# RFIDAccess.net
KiCad netlist of a schematic drawn in EAGLE
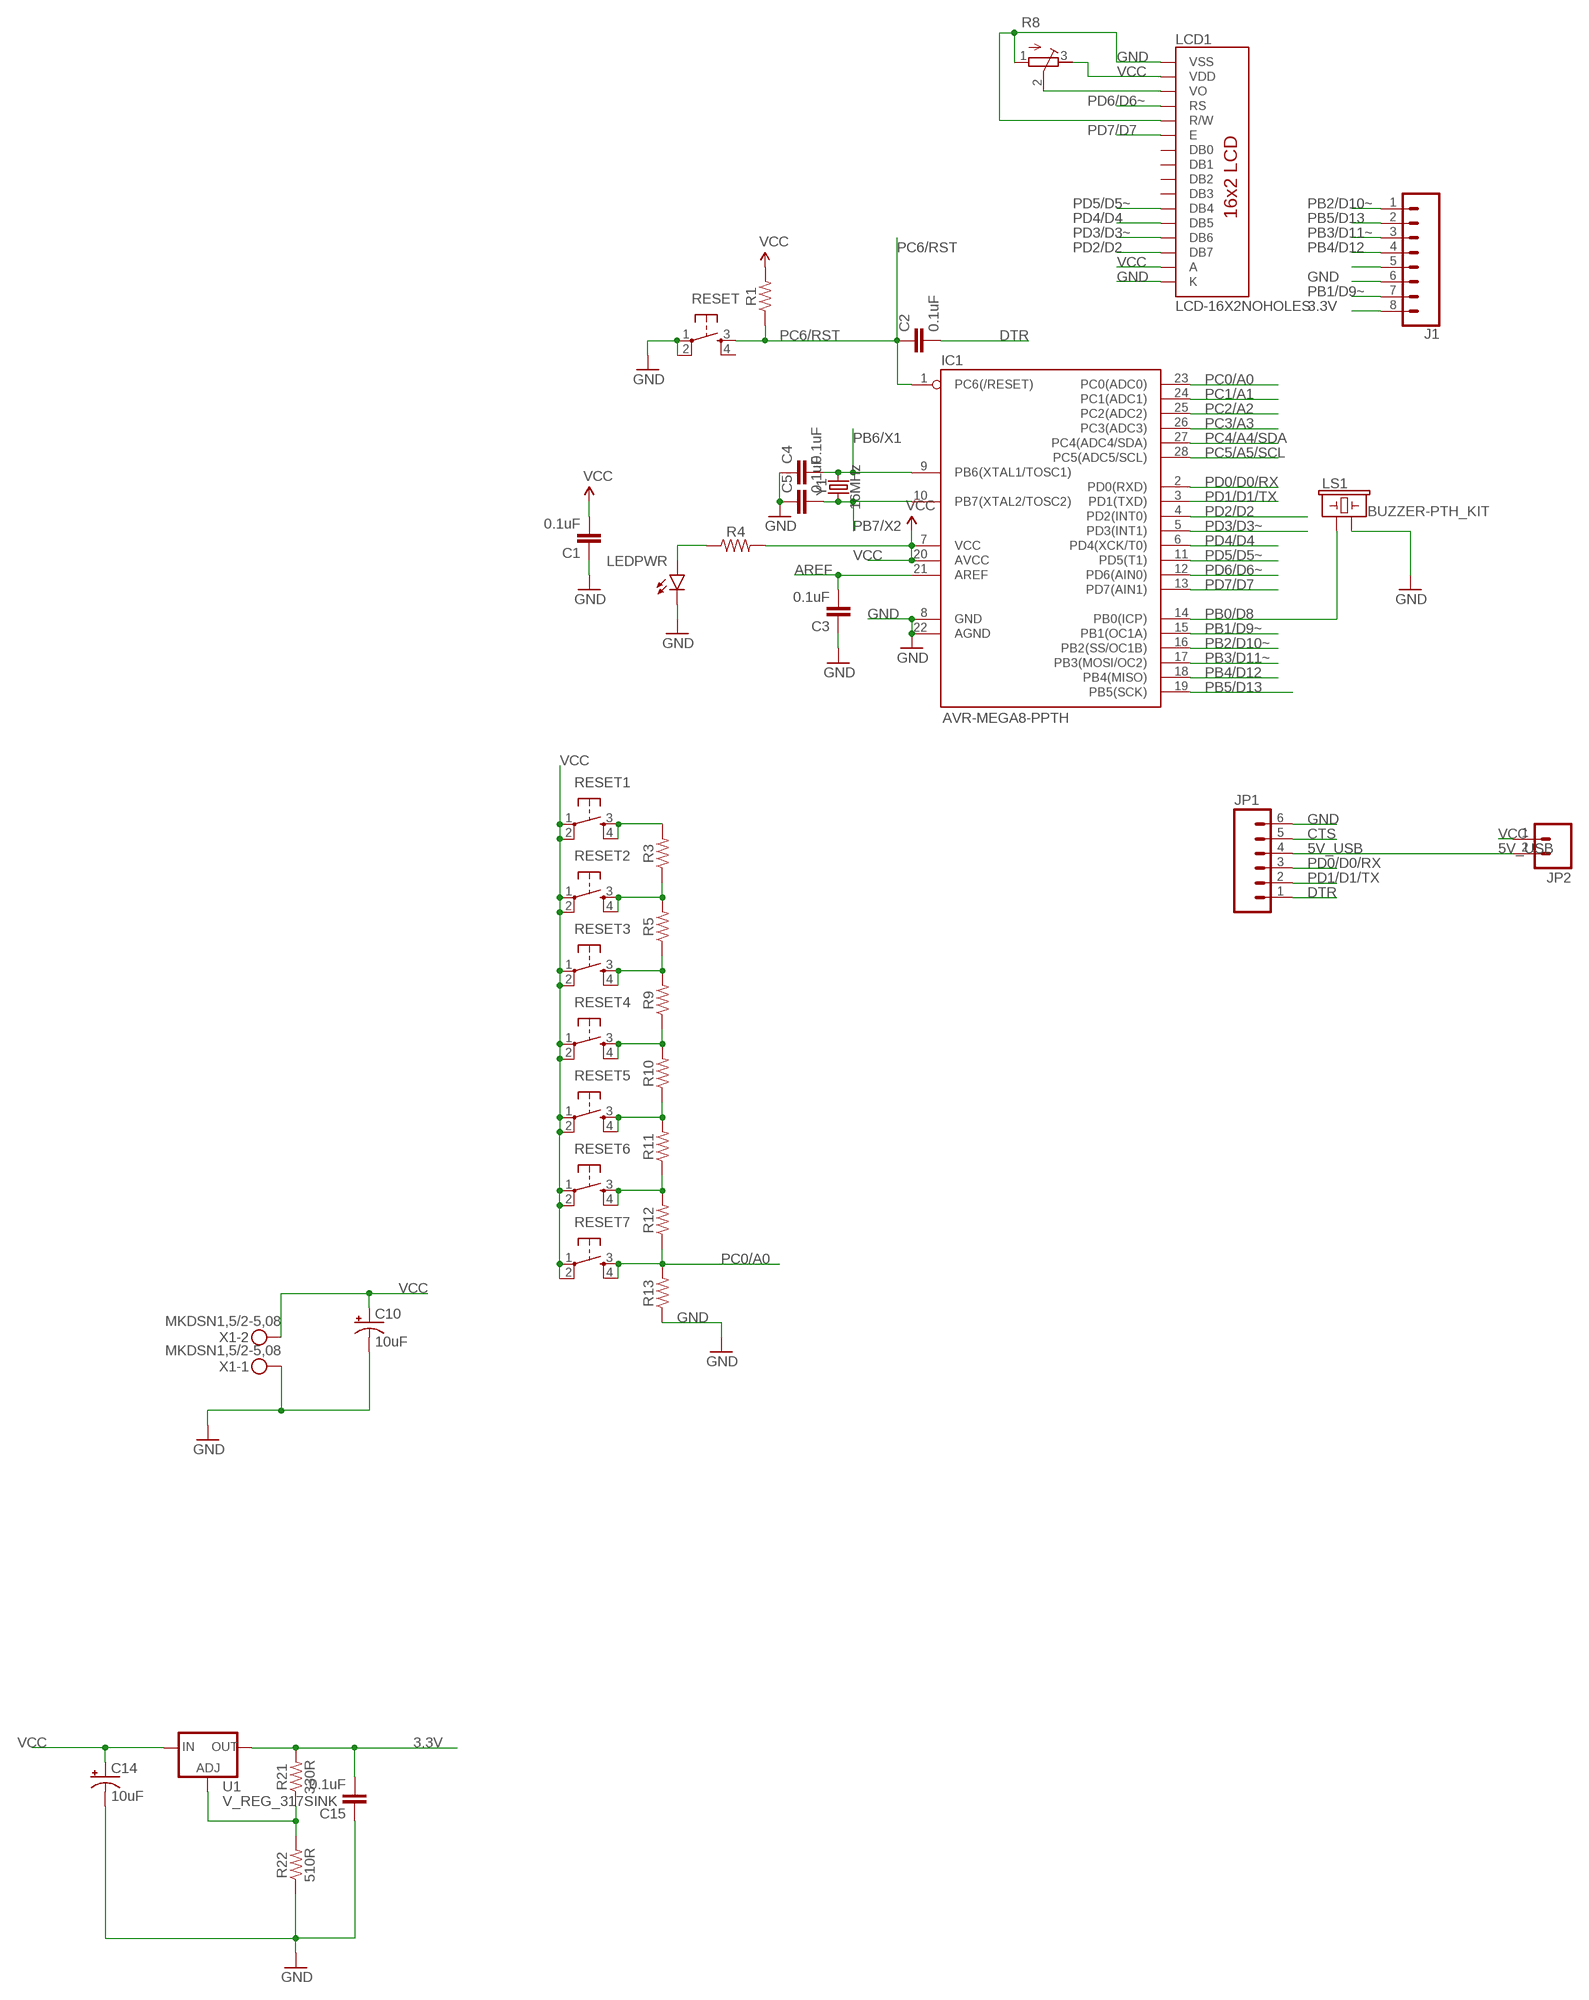
[diagram p0: schematic, sheet 1]

(export (version "E")
  (design (tool "Eeschema 10.0.6"))
  (components
    (comp (ref "C1")
      (value "0.1uF")
      (footprint "eagle-import:CAP-PTH-SMALL-KIT")
      (libsource (lib "eagle-import") (part "0.1UF-KIT-EZ-50V-20%"))
    )
    (comp (ref "C2")
      (value "0.1uF")
      (footprint "eagle-import:CAP-PTH-SMALL-KIT")
      (libsource (lib "eagle-import") (part "0.1UF-KIT-EZ-50V-20%"))
    )
    (comp (ref "C3")
      (value "0.1uF")
      (footprint "eagle-import:CAP-PTH-SMALL-KIT")
      (libsource (lib "eagle-import") (part "0.1UF-KIT-EZ-50V-20%"))
    )
    (comp (ref "C4")
      (value "0.1uF")
      (footprint "eagle-import:CAP-PTH-SMALL-KIT")
      (libsource (lib "eagle-import") (part "0.1UF-KIT-EZ-50V-20%"))
    )
    (comp (ref "C5")
      (value "0.1uF")
      (footprint "eagle-import:CAP-PTH-SMALL-KIT")
      (libsource (lib "eagle-import") (part "0.1UF-KIT-EZ-50V-20%"))
    )
    (comp (ref "C10")
      (value "10uF")
      (footprint "eagle-import:CPOL-RADIAL-2.5MM-5MM-KIT")
      (libsource (lib "eagle-import") (part "10UF-POLAR-RADIAL-2.5MM-KIT-25V-20%"))
    )
    (comp (ref "C14")
      (value "10uF")
      (footprint "eagle-import:CPOL-RADIAL-2.5MM-5MM-KIT")
      (libsource (lib "eagle-import") (part "10UF-POLAR-RADIAL-2.5MM-KIT-25V-20%"))
    )
    (comp (ref "C15")
      (value "0.1uF")
      (footprint "eagle-import:CAP-PTH-SMALL-KIT")
      (libsource (lib "eagle-import") (part "0.1UF-KIT-EZ-50V-20%"))
    )
    (comp (ref "IC1")
      (value "AVR-MEGA8-PPTH")
      (footprint "eagle-import:DIL28-3")
      (libsource (lib "eagle-import") (part "AVR-MEGA8-PPTH"))
    )
    (comp (ref "J1")
      (value "CONN_08LONGPADS")
      (footprint "eagle-import:1X08_LONGPADS")
      (libsource (lib "eagle-import") (part "CONN_08LONGPADS"))
    )
    (comp (ref "JP1")
      (value "M06SIP")
      (footprint "eagle-import:1X06")
      (libsource (lib "eagle-import") (part "M06SIP"))
    )
    (comp (ref "JP2")
      (value "M02PTH")
      (footprint "eagle-import:1X02")
      (libsource (lib "eagle-import") (part "M02PTH"))
    )
    (comp (ref "LCD1")
      (value "LCD-16X2NOHOLES")
      (footprint "eagle-import:LCD-16X2_NOHOLESNOSILK")
      (libsource (lib "eagle-import") (part "LCD-16X2NOHOLES"))
    )
    (comp (ref "LEDPWR")
      (value "LED5MM-KIT")
      (footprint "eagle-import:LED_5MM-KIT")
      (libsource (lib "eagle-import") (part "LED5MM-KIT"))
    )
    (comp (ref "LS1")
      (value "BUZZER-PTH_KIT")
      (footprint "eagle-import:BUZZER-12MM-KIT")
      (libsource (lib "eagle-import") (part "BUZZER-PTH_KIT"))
    )
    (comp (ref "R1")
      (value "RESISTORAXIAL-0.3-KIT")
      (footprint "eagle-import:AXIAL-0.3-KIT")
      (libsource (lib "eagle-import") (part "RESISTORAXIAL-0.3-KIT"))
    )
    (comp (ref "R3")
      (value "RESISTORAXIAL-0.3-KIT")
      (footprint "eagle-import:AXIAL-0.3-KIT")
      (libsource (lib "eagle-import") (part "RESISTORAXIAL-0.3-KIT"))
    )
    (comp (ref "R4")
      (value "RESISTORAXIAL-0.3-KIT")
      (footprint "eagle-import:AXIAL-0.3-KIT")
      (libsource (lib "eagle-import") (part "RESISTORAXIAL-0.3-KIT"))
    )
    (comp (ref "R5")
      (value "RESISTORAXIAL-0.3-KIT")
      (footprint "eagle-import:AXIAL-0.3-KIT")
      (libsource (lib "eagle-import") (part "RESISTORAXIAL-0.3-KIT"))
    )
    (comp (ref "R8")
      (value "R-TRIMM3296W")
      (footprint "eagle-import:RTRIM3296W")
      (libsource (lib "eagle-import") (part "R-TRIMM3296W"))
    )
    (comp (ref "R9")
      (value "RESISTORAXIAL-0.3-KIT")
      (footprint "eagle-import:AXIAL-0.3-KIT")
      (libsource (lib "eagle-import") (part "RESISTORAXIAL-0.3-KIT"))
    )
    (comp (ref "R10")
      (value "RESISTORAXIAL-0.3-KIT")
      (footprint "eagle-import:AXIAL-0.3-KIT")
      (libsource (lib "eagle-import") (part "RESISTORAXIAL-0.3-KIT"))
    )
    (comp (ref "R11")
      (value "RESISTORAXIAL-0.3-KIT")
      (footprint "eagle-import:AXIAL-0.3-KIT")
      (libsource (lib "eagle-import") (part "RESISTORAXIAL-0.3-KIT"))
    )
    (comp (ref "R12")
      (value "RESISTORAXIAL-0.3-KIT")
      (footprint "eagle-import:AXIAL-0.3-KIT")
      (libsource (lib "eagle-import") (part "RESISTORAXIAL-0.3-KIT"))
    )
    (comp (ref "R13")
      (value "RESISTORAXIAL-0.3-KIT")
      (footprint "eagle-import:AXIAL-0.3-KIT")
      (libsource (lib "eagle-import") (part "RESISTORAXIAL-0.3-KIT"))
    )
    (comp (ref "R21")
      (value "330R")
      (footprint "eagle-import:AXIAL-0.3-KIT")
      (libsource (lib "eagle-import") (part "RESISTORAXIAL-0.3-KIT"))
    )
    (comp (ref "R22")
      (value "510R")
      (footprint "eagle-import:AXIAL-0.3-KIT")
      (libsource (lib "eagle-import") (part "RESISTORAXIAL-0.3-KIT"))
    )
    (comp (ref "RESET")
      (value "TAC_SWITCHPTH")
      (footprint "eagle-import:TACTILE-PTH")
      (libsource (lib "eagle-import") (part "TAC_SWITCHPTH"))
    )
    (comp (ref "RESET1")
      (value "TAC_SWITCHPTH")
      (footprint "eagle-import:TACTILE-PTH")
      (libsource (lib "eagle-import") (part "TAC_SWITCHPTH"))
    )
    (comp (ref "RESET2")
      (value "TAC_SWITCHPTH")
      (footprint "eagle-import:TACTILE-PTH")
      (libsource (lib "eagle-import") (part "TAC_SWITCHPTH"))
    )
    (comp (ref "RESET3")
      (value "TAC_SWITCHPTH")
      (footprint "eagle-import:TACTILE-PTH")
      (libsource (lib "eagle-import") (part "TAC_SWITCHPTH"))
    )
    (comp (ref "RESET4")
      (value "TAC_SWITCHPTH")
      (footprint "eagle-import:TACTILE-PTH")
      (libsource (lib "eagle-import") (part "TAC_SWITCHPTH"))
    )
    (comp (ref "RESET5")
      (value "TAC_SWITCHPTH")
      (footprint "eagle-import:TACTILE-PTH")
      (libsource (lib "eagle-import") (part "TAC_SWITCHPTH"))
    )
    (comp (ref "RESET6")
      (value "TAC_SWITCHPTH")
      (footprint "eagle-import:TACTILE-PTH")
      (libsource (lib "eagle-import") (part "TAC_SWITCHPTH"))
    )
    (comp (ref "RESET7")
      (value "TAC_SWITCHPTH")
      (footprint "eagle-import:TACTILE-PTH")
      (libsource (lib "eagle-import") (part "TAC_SWITCHPTH"))
    )
    (comp (ref "U1")
      (value "V_REG_317SINK")
      (footprint "eagle-import:TO220-ADJ")
      (libsource (lib "eagle-import") (part "V_REG_317SINK"))
    )
    (comp (ref "X1")
      (value "MKDSN1,5/2-5,08")
      (footprint "eagle-import:MKDSN1,5_2-5,08")
      (libsource (lib "eagle-import") (part "MKDSN1,5/2-5,08"))
    )
    (comp (ref "Y1")
      (value "16MHz")
      (footprint "eagle-import:HC49US")
      (libsource (lib "eagle-import") (part "CRYSTAL-16MHZPTH-HC49US"))
    )
  )
  (nets
    (net (code "1") (name "/3.3V") (class "Default")
      (node (ref "C15") (pin "2") (pinfunction "2_2") (pintype "passive"))
      (node (ref "J1") (pin "8") (pinfunction "8_8") (pintype "passive"))
      (node (ref "R21") (pin "P$2") (pinfunction "2_P$2") (pintype "passive"))
      (node (ref "U1") (pin "OUT") (pinfunction "OUT_OUT") (pintype "output"))
    )
    (net (code "2") (name "/5V_USB") (class "Default")
      (node (ref "JP1") (pin "4") (pinfunction "4_4") (pintype "passive"))
      (node (ref "JP2") (pin "2") (pinfunction "2_2") (pintype "passive"))
    )
    (net (code "3") (name "/AREF") (class "Default")
      (node (ref "C3") (pin "2") (pinfunction "2_2") (pintype "passive"))
      (node (ref "IC1") (pin "21") (pinfunction "AREF_21") (pintype "bidirectional"))
    )
    (net (code "4") (name "/CTS") (class "Default")
      (node (ref "JP1") (pin "5") (pinfunction "5_5") (pintype "passive"))
    )
    (net (code "5") (name "/DTR") (class "Default")
      (node (ref "C2") (pin "2") (pinfunction "2_2") (pintype "passive"))
      (node (ref "JP1") (pin "1") (pinfunction "1_1") (pintype "passive"))
    )
    (net (code "6") (name "/PB0{slash}D8") (class "Default")
      (node (ref "IC1") (pin "14") (pinfunction "PB0(ICP)_14") (pintype "bidirectional"))
      (node (ref "LS1") (pin "+") (pinfunction "1_+") (pintype "passive"))
    )
    (net (code "7") (name "/PB1{slash}D9~{}") (class "Default")
      (node (ref "IC1") (pin "15") (pinfunction "PB1(OC1A)_15") (pintype "bidirectional"))
      (node (ref "J1") (pin "7") (pinfunction "7_7") (pintype "passive"))
    )
    (net (code "8") (name "/PB2{slash}D10~{}") (class "Default")
      (node (ref "IC1") (pin "16") (pinfunction "PB2(SS/OC1B)_16") (pintype "bidirectional"))
      (node (ref "J1") (pin "1") (pinfunction "1_1") (pintype "passive"))
    )
    (net (code "9") (name "/PB3{slash}D11~{}") (class "Default")
      (node (ref "IC1") (pin "17") (pinfunction "PB3(MOSI/OC2)_17") (pintype "bidirectional"))
      (node (ref "J1") (pin "3") (pinfunction "3_3") (pintype "passive"))
    )
    (net (code "10") (name "/PB4{slash}D12") (class "Default")
      (node (ref "IC1") (pin "18") (pinfunction "PB4(MISO)_18") (pintype "bidirectional"))
      (node (ref "J1") (pin "4") (pinfunction "4_4") (pintype "passive"))
    )
    (net (code "11") (name "/PB5{slash}D13") (class "Default")
      (node (ref "IC1") (pin "19") (pinfunction "PB5(SCK)_19") (pintype "bidirectional"))
      (node (ref "J1") (pin "2") (pinfunction "2_2") (pintype "passive"))
    )
    (net (code "12") (name "/PB6{slash}X1") (class "Default")
      (node (ref "C4") (pin "2") (pinfunction "2_2") (pintype "passive"))
      (node (ref "IC1") (pin "9") (pinfunction "PB6(XTAL1/TOSC1)_9") (pintype "bidirectional"))
      (node (ref "Y1") (pin "2") (pinfunction "2_2") (pintype "passive"))
    )
    (net (code "13") (name "/PB7{slash}X2") (class "Default")
      (node (ref "C5") (pin "2") (pinfunction "2_2") (pintype "passive"))
      (node (ref "IC1") (pin "10") (pinfunction "PB7(XTAL2/TOSC2)_10") (pintype "bidirectional"))
      (node (ref "Y1") (pin "1") (pinfunction "1_1") (pintype "passive"))
    )
    (net (code "14") (name "/PC0{slash}A0") (class "Default")
      (node (ref "IC1") (pin "23") (pinfunction "PC0(ADC0)_23") (pintype "bidirectional"))
      (node (ref "R12") (pin "P$1") (pinfunction "1_P$1") (pintype "passive"))
      (node (ref "R13") (pin "P$2") (pinfunction "2_P$2") (pintype "passive"))
      (node (ref "RESET7") (pin "3") (pinfunction "3_3") (pintype "passive"))
      (node (ref "RESET7") (pin "4") (pinfunction "4_4") (pintype "passive"))
    )
    (net (code "15") (name "/PC1{slash}A1") (class "Default")
      (node (ref "IC1") (pin "24") (pinfunction "PC1(ADC1)_24") (pintype "bidirectional"))
    )
    (net (code "16") (name "/PC2{slash}A2") (class "Default")
      (node (ref "IC1") (pin "25") (pinfunction "PC2(ADC2)_25") (pintype "bidirectional"))
    )
    (net (code "17") (name "/PC3{slash}A3") (class "Default")
      (node (ref "IC1") (pin "26") (pinfunction "PC3(ADC3)_26") (pintype "bidirectional"))
    )
    (net (code "18") (name "/PC4{slash}A4{slash}SDA") (class "Default")
      (node (ref "IC1") (pin "27") (pinfunction "PC4(ADC4/SDA)_27") (pintype "bidirectional"))
    )
    (net (code "19") (name "/PC5{slash}A5{slash}SCL") (class "Default")
      (node (ref "IC1") (pin "28") (pinfunction "PC5(ADC5/SCL)_28") (pintype "bidirectional"))
    )
    (net (code "20") (name "/PC6{slash}RST") (class "Default")
      (node (ref "C2") (pin "1") (pinfunction "1_1") (pintype "passive"))
      (node (ref "IC1") (pin "1") (pinfunction "PC6(/RESET)_1") (pintype "bidirectional"))
      (node (ref "R1") (pin "P$1") (pinfunction "1_P$1") (pintype "passive"))
      (node (ref "RESET") (pin "3") (pinfunction "3_3") (pintype "passive"))
    )
    (net (code "21") (name "/PD0{slash}D0{slash}RX") (class "Default")
      (node (ref "IC1") (pin "2") (pinfunction "PD0(RXD)_2") (pintype "bidirectional"))
      (node (ref "JP1") (pin "3") (pinfunction "3_3") (pintype "passive"))
    )
    (net (code "22") (name "/PD1{slash}D1{slash}TX") (class "Default")
      (node (ref "IC1") (pin "3") (pinfunction "PD1(TXD)_3") (pintype "bidirectional"))
      (node (ref "JP1") (pin "2") (pinfunction "2_2") (pintype "passive"))
    )
    (net (code "23") (name "/PD2{slash}D2") (class "Default")
      (node (ref "IC1") (pin "4") (pinfunction "PD2(INT0)_4") (pintype "bidirectional"))
      (node (ref "LCD1") (pin "14") (pinfunction "DB7_14") (pintype "bidirectional"))
    )
    (net (code "24") (name "/PD3{slash}D3~{}") (class "Default")
      (node (ref "IC1") (pin "5") (pinfunction "PD3(INT1)_5") (pintype "bidirectional"))
      (node (ref "LCD1") (pin "13") (pinfunction "DB6_13") (pintype "bidirectional"))
    )
    (net (code "25") (name "/PD4{slash}D4") (class "Default")
      (node (ref "IC1") (pin "6") (pinfunction "PD4(XCK/T0)_6") (pintype "bidirectional"))
      (node (ref "LCD1") (pin "12") (pinfunction "DB5_12") (pintype "bidirectional"))
    )
    (net (code "26") (name "/PD5{slash}D5~{}") (class "Default")
      (node (ref "IC1") (pin "11") (pinfunction "PD5(T1)_11") (pintype "bidirectional"))
      (node (ref "LCD1") (pin "11") (pinfunction "DB4_11") (pintype "bidirectional"))
    )
    (net (code "27") (name "/PD6{slash}D6~{}") (class "Default")
      (node (ref "IC1") (pin "12") (pinfunction "PD6(AIN0)_12") (pintype "bidirectional"))
      (node (ref "LCD1") (pin "4") (pinfunction "RS_4") (pintype "input"))
    )
    (net (code "28") (name "/PD7{slash}D7") (class "Default")
      (node (ref "IC1") (pin "13") (pinfunction "PD7(AIN1)_13") (pintype "bidirectional"))
      (node (ref "LCD1") (pin "6") (pinfunction "E_6") (pintype "input"))
    )
    (net (code "29") (name "GND") (class "Default")
      (node (ref "C1") (pin "1") (pinfunction "1_1") (pintype "passive"))
      (node (ref "C10") (pin "2") (pinfunction "-_2") (pintype "passive"))
      (node (ref "C14") (pin "2") (pinfunction "-_2") (pintype "passive"))
      (node (ref "C15") (pin "1") (pinfunction "1_1") (pintype "passive"))
      (node (ref "C3") (pin "1") (pinfunction "1_1") (pintype "passive"))
      (node (ref "C4") (pin "1") (pinfunction "1_1") (pintype "passive"))
      (node (ref "C5") (pin "1") (pinfunction "1_1") (pintype "passive"))
      (node (ref "IC1") (pin "22") (pinfunction "AGND_22") (pintype "bidirectional"))
      (node (ref "IC1") (pin "8") (pinfunction "GND_8") (pintype "bidirectional"))
      (node (ref "J1") (pin "6") (pinfunction "6_6") (pintype "passive"))
      (node (ref "JP1") (pin "6") (pinfunction "6_6") (pintype "passive"))
      (node (ref "LCD1") (pin "1") (pinfunction "VSS_1") (pintype "power_in"))
      (node (ref "LCD1") (pin "16") (pinfunction "K_16") (pintype "power_in"))
      (node (ref "LCD1") (pin "5") (pinfunction "R/W_5") (pintype "input"))
      (node (ref "LEDPWR") (pin "K") (pinfunction "C_K") (pintype "passive"))
      (node (ref "LS1") (pin "-") (pinfunction "2_-") (pintype "passive"))
      (node (ref "R13") (pin "P$1") (pinfunction "1_P$1") (pintype "passive"))
      (node (ref "R22") (pin "P$1") (pinfunction "1_P$1") (pintype "passive"))
      (node (ref "R8") (pin "1") (pinfunction "A_1") (pintype "passive"))
      (node (ref "RESET") (pin "1") (pinfunction "1_1") (pintype "passive"))
      (node (ref "RESET") (pin "2") (pinfunction "2_2") (pintype "passive"))
      (node (ref "X1") (pin "1") (pinfunction "KL_1") (pintype "passive"))
    )
    (net (code "30") (name "Net-(LCD1-VO)") (class "Default")
      (node (ref "LCD1") (pin "3") (pinfunction "VO_3") (pintype "bidirectional"))
      (node (ref "R8") (pin "2") (pinfunction "S_2") (pintype "passive"))
    )
    (net (code "31") (name "Net-(R3-1)") (class "Default")
      (node (ref "R3") (pin "P$1") (pinfunction "1_P$1") (pintype "passive"))
      (node (ref "R5") (pin "P$2") (pinfunction "2_P$2") (pintype "passive"))
      (node (ref "RESET2") (pin "3") (pinfunction "3_3") (pintype "passive"))
      (node (ref "RESET2") (pin "4") (pinfunction "4_4") (pintype "passive"))
    )
    (net (code "32") (name "Net-(R3-2)") (class "Default")
      (node (ref "R3") (pin "P$2") (pinfunction "2_P$2") (pintype "passive"))
      (node (ref "RESET1") (pin "3") (pinfunction "3_3") (pintype "passive"))
      (node (ref "RESET1") (pin "4") (pinfunction "4_4") (pintype "passive"))
    )
    (net (code "33") (name "Net-(R4-1)") (class "Default")
      (node (ref "LEDPWR") (pin "A") (pinfunction "A_A") (pintype "passive"))
      (node (ref "R4") (pin "P$1") (pinfunction "1_P$1") (pintype "passive"))
    )
    (net (code "34") (name "Net-(R5-1)") (class "Default")
      (node (ref "R5") (pin "P$1") (pinfunction "1_P$1") (pintype "passive"))
      (node (ref "R9") (pin "P$2") (pinfunction "2_P$2") (pintype "passive"))
      (node (ref "RESET3") (pin "3") (pinfunction "3_3") (pintype "passive"))
      (node (ref "RESET3") (pin "4") (pinfunction "4_4") (pintype "passive"))
    )
    (net (code "35") (name "Net-(R10-1)") (class "Default")
      (node (ref "R10") (pin "P$1") (pinfunction "1_P$1") (pintype "passive"))
      (node (ref "R11") (pin "P$2") (pinfunction "2_P$2") (pintype "passive"))
      (node (ref "RESET5") (pin "3") (pinfunction "3_3") (pintype "passive"))
      (node (ref "RESET5") (pin "4") (pinfunction "4_4") (pintype "passive"))
    )
    (net (code "36") (name "Net-(R10-2)") (class "Default")
      (node (ref "R10") (pin "P$2") (pinfunction "2_P$2") (pintype "passive"))
      (node (ref "R9") (pin "P$1") (pinfunction "1_P$1") (pintype "passive"))
      (node (ref "RESET4") (pin "3") (pinfunction "3_3") (pintype "passive"))
      (node (ref "RESET4") (pin "4") (pinfunction "4_4") (pintype "passive"))
    )
    (net (code "37") (name "Net-(R11-1)") (class "Default")
      (node (ref "R11") (pin "P$1") (pinfunction "1_P$1") (pintype "passive"))
      (node (ref "R12") (pin "P$2") (pinfunction "2_P$2") (pintype "passive"))
      (node (ref "RESET6") (pin "3") (pinfunction "3_3") (pintype "passive"))
      (node (ref "RESET6") (pin "4") (pinfunction "4_4") (pintype "passive"))
    )
    (net (code "38") (name "Net-(R21-1)") (class "Default")
      (node (ref "R21") (pin "P$1") (pinfunction "1_P$1") (pintype "passive"))
      (node (ref "R22") (pin "P$2") (pinfunction "2_P$2") (pintype "passive"))
      (node (ref "U1") (pin "ADJ") (pinfunction "ADJ_ADJ") (pintype "input"))
    )
    (net (code "39") (name "VCC") (class "Default")
      (node (ref "C1") (pin "2") (pinfunction "2_2") (pintype "passive"))
      (node (ref "C10") (pin "1") (pinfunction "+_1") (pintype "passive"))
      (node (ref "C14") (pin "1") (pinfunction "+_1") (pintype "passive"))
      (node (ref "IC1") (pin "20") (pinfunction "AVCC_20") (pintype "bidirectional"))
      (node (ref "IC1") (pin "7") (pinfunction "VCC_7") (pintype "bidirectional"))
      (node (ref "JP2") (pin "1") (pinfunction "1_1") (pintype "passive"))
      (node (ref "LCD1") (pin "15") (pinfunction "A_15") (pintype "power_in"))
      (node (ref "LCD1") (pin "2") (pinfunction "VDD_2") (pintype "power_in"))
      (node (ref "R1") (pin "P$2") (pinfunction "2_P$2") (pintype "passive"))
      (node (ref "R4") (pin "P$2") (pinfunction "2_P$2") (pintype "passive"))
      (node (ref "R8") (pin "3") (pinfunction "E_3") (pintype "passive"))
      (node (ref "RESET1") (pin "1") (pinfunction "1_1") (pintype "passive"))
      (node (ref "RESET1") (pin "2") (pinfunction "2_2") (pintype "passive"))
      (node (ref "RESET2") (pin "1") (pinfunction "1_1") (pintype "passive"))
      (node (ref "RESET2") (pin "2") (pinfunction "2_2") (pintype "passive"))
      (node (ref "RESET3") (pin "1") (pinfunction "1_1") (pintype "passive"))
      (node (ref "RESET3") (pin "2") (pinfunction "2_2") (pintype "passive"))
      (node (ref "RESET4") (pin "1") (pinfunction "1_1") (pintype "passive"))
      (node (ref "RESET4") (pin "2") (pinfunction "2_2") (pintype "passive"))
      (node (ref "RESET5") (pin "1") (pinfunction "1_1") (pintype "passive"))
      (node (ref "RESET5") (pin "2") (pinfunction "2_2") (pintype "passive"))
      (node (ref "RESET6") (pin "1") (pinfunction "1_1") (pintype "passive"))
      (node (ref "RESET6") (pin "2") (pinfunction "2_2") (pintype "passive"))
      (node (ref "RESET7") (pin "1") (pinfunction "1_1") (pintype "passive"))
      (node (ref "RESET7") (pin "2") (pinfunction "2_2") (pintype "passive"))
      (node (ref "U1") (pin "IN") (pinfunction "IN_IN") (pintype "input"))
      (node (ref "X1") (pin "2") (pinfunction "KL_2") (pintype "passive"))
    )
    (net (code "40") (name "unconnected-(J1-Pad5)") (class "Default")
      (node (ref "J1") (pin "5") (pinfunction "5_5") (pintype "passive"))
    )
    (net (code "41") (name "unconnected-(LCD1-DB0-Pad7)") (class "Default")
      (node (ref "LCD1") (pin "7") (pinfunction "DB0_7") (pintype "bidirectional"))
    )
    (net (code "42") (name "unconnected-(LCD1-DB1-Pad8)") (class "Default")
      (node (ref "LCD1") (pin "8") (pinfunction "DB1_8") (pintype "bidirectional"))
    )
    (net (code "43") (name "unconnected-(LCD1-DB2-Pad9)") (class "Default")
      (node (ref "LCD1") (pin "9") (pinfunction "DB2_9") (pintype "bidirectional"))
    )
    (net (code "44") (name "unconnected-(LCD1-DB3-Pad10)") (class "Default")
      (node (ref "LCD1") (pin "10") (pinfunction "DB3_10") (pintype "bidirectional"))
    )
    (net (code "45") (name "unconnected-(RESET-Pad4)") (class "Default")
      (node (ref "RESET") (pin "4") (pinfunction "4_4") (pintype "passive"))
    )
  )
)
